# Tiva_Control.net
KiCad netlist of a schematic drawn in Altium Designer
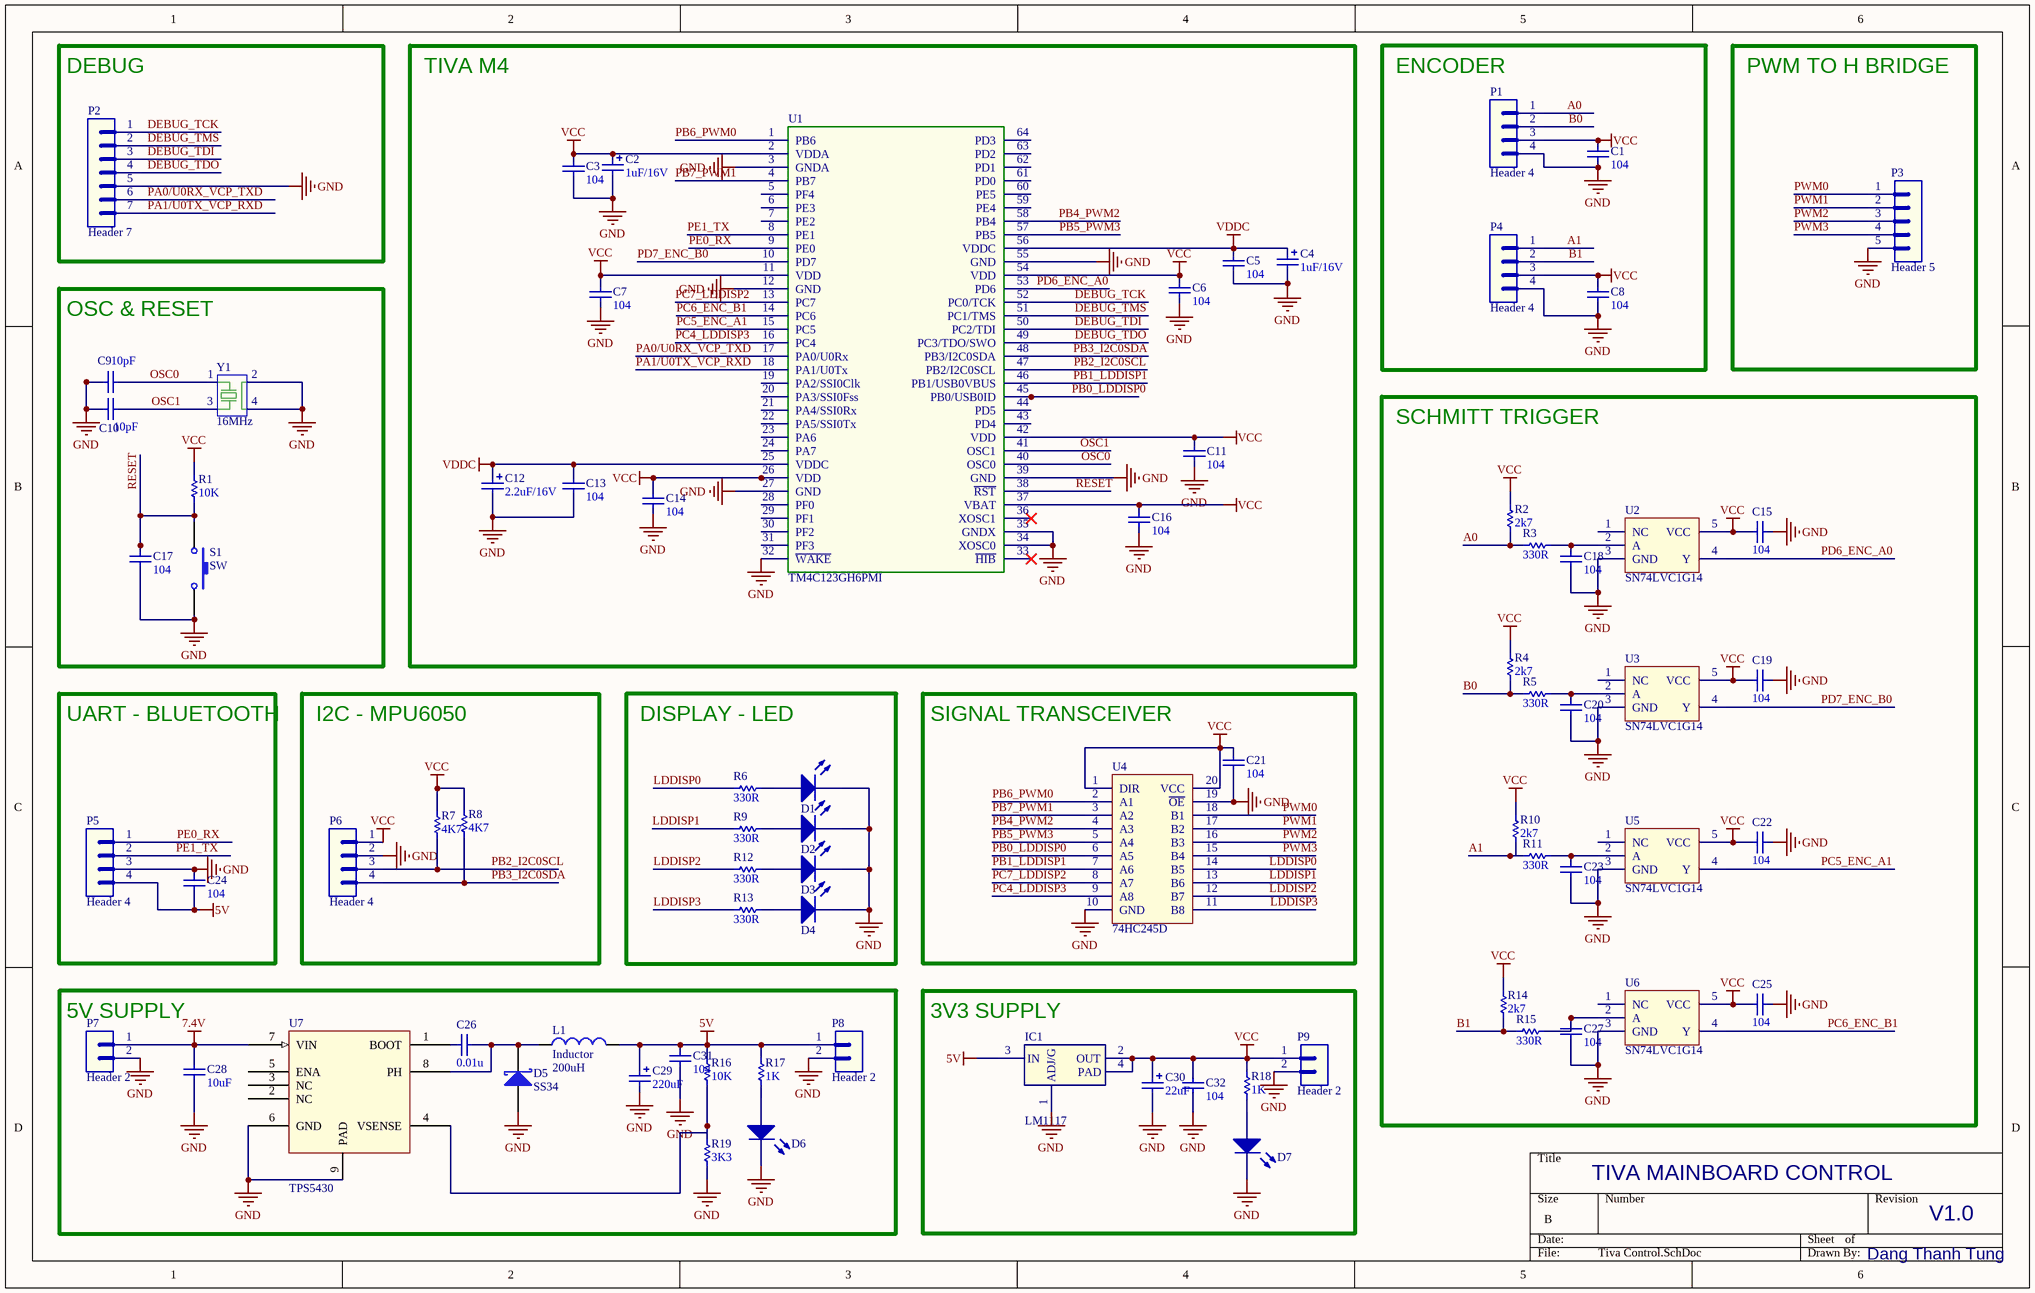
[diagram p0: Tiva Control.SchDoc]

(export (version "E")
  (design (tool "Eeschema 10.0.6"))
  (components
    (comp (ref "C1")
      (value "104")
      (footprint "CAP-SM-0805")
      (description "Capacitor")
      (fields (field (name "Comment") "Cap Non-Pol SMD"))
      (libsource (lib "minht57_lib") (part "Cap Non-Pol SMD"))
    )
    (comp (ref "C2")
      (value "Capacitors")
      (footprint "CAP TANTALUM SMD-1206")
      (description "Capacitors Tantalum")
      (fields
        (field (name "MANUFACTURER") "Kemet")
        (field (name "MANUFACTURER PART NUMBER") "T491A106K010AT")
        (field (name "CAPACITANCE") "1uF/16V")
      )
      (libsource (lib "minht57_lib") (part "Cap Pol Tantalum"))
    )
    (comp (ref "C3")
      (value "104")
      (footprint "CAP-SM-0805")
      (description "Capacitor")
      (fields (field (name "Comment") "Cap Non-Pol SMD"))
      (libsource (lib "minht57_lib") (part "Cap Non-Pol SMD"))
    )
    (comp (ref "C4")
      (value "Capacitors")
      (footprint "CAP TANTALUM SMD-1206")
      (description "Capacitors Tantalum")
      (fields
        (field (name "MANUFACTURER") "Kemet")
        (field (name "MANUFACTURER PART NUMBER") "T491A106K010AT")
        (field (name "CAPACITANCE") "1uF/16V")
      )
      (libsource (lib "minht57_lib") (part "Cap Pol Tantalum"))
    )
    (comp (ref "C5")
      (value "104")
      (footprint "CAP-SM-0805")
      (description "Capacitor")
      (fields (field (name "Comment") "Cap Non-Pol SMD"))
      (libsource (lib "minht57_lib") (part "Cap Non-Pol SMD"))
    )
    (comp (ref "C6")
      (value "104")
      (footprint "CAP-SM-0805")
      (description "Capacitor")
      (fields (field (name "Comment") "Cap Non-Pol SMD"))
      (libsource (lib "minht57_lib") (part "Cap Non-Pol SMD"))
    )
    (comp (ref "C7")
      (value "104")
      (footprint "CAP-SM-0805")
      (description "Capacitor")
      (fields (field (name "Comment") "Cap Non-Pol SMD"))
      (libsource (lib "minht57_lib") (part "Cap Non-Pol SMD"))
    )
    (comp (ref "C8")
      (value "104")
      (footprint "CAP-SM-0805")
      (description "Capacitor")
      (fields (field (name "Comment") "Cap Non-Pol SMD"))
      (libsource (lib "minht57_lib") (part "Cap Non-Pol SMD"))
    )
    (comp (ref "C9")
      (value "10pF")
      (footprint "CAP-SM-0805")
      (description "Capacitor")
      (fields (field (name "Comment") "Cap Non-Pol SMD"))
      (libsource (lib "minht57_lib") (part "Cap Non-Pol SMD"))
    )
    (comp (ref "C10")
      (value "10pF")
      (footprint "CAP-SM-0805")
      (description "Capacitor")
      (fields (field (name "Comment") "Cap Non-Pol SMD"))
      (libsource (lib "minht57_lib") (part "Cap Non-Pol SMD"))
    )
    (comp (ref "C11")
      (value "104")
      (footprint "CAP-SM-0805")
      (description "Capacitor")
      (fields (field (name "Comment") "Cap Non-Pol SMD"))
      (libsource (lib "minht57_lib") (part "Cap Non-Pol SMD"))
    )
    (comp (ref "C12")
      (value "Capacitors")
      (footprint "CAP TANTALUM SMD-1206")
      (description "Capacitors Tantalum")
      (fields
        (field (name "MANUFACTURER") "Kemet")
        (field (name "MANUFACTURER PART NUMBER") "T491A106K010AT")
        (field (name "CAPACITANCE") "2.2uF/16V")
      )
      (libsource (lib "minht57_lib") (part "Cap Pol Tantalum"))
    )
    (comp (ref "C13")
      (value "104")
      (footprint "CAP-SM-0805")
      (description "Capacitor")
      (fields (field (name "Comment") "Cap Non-Pol SMD"))
      (libsource (lib "minht57_lib") (part "Cap Non-Pol SMD"))
    )
    (comp (ref "C14")
      (value "104")
      (footprint "CAP-SM-0805")
      (description "Capacitor")
      (fields (field (name "Comment") "Cap Non-Pol SMD"))
      (libsource (lib "minht57_lib") (part "Cap Non-Pol SMD"))
    )
    (comp (ref "C15")
      (value "104")
      (footprint "CAP-SM-0805")
      (description "Capacitor")
      (fields (field (name "Comment") "Cap Non-Pol SMD"))
      (libsource (lib "minht57_lib") (part "Cap Non-Pol SMD"))
    )
    (comp (ref "C16")
      (value "104")
      (footprint "CAP-SM-0805")
      (description "Capacitor")
      (fields (field (name "Comment") "Cap Non-Pol SMD"))
      (libsource (lib "minht57_lib") (part "Cap Non-Pol SMD"))
    )
    (comp (ref "C17")
      (value "104")
      (footprint "CAP-SM-0805")
      (description "Capacitor")
      (fields (field (name "Comment") "Cap Non-Pol SMD"))
      (libsource (lib "minht57_lib") (part "Cap Non-Pol SMD"))
    )
    (comp (ref "C18")
      (value "104")
      (footprint "CAP-SM-0805")
      (description "Capacitor")
      (fields (field (name "Comment") "Cap Non-Pol SMD"))
      (libsource (lib "minht57_lib") (part "Cap Non-Pol SMD"))
    )
    (comp (ref "C19")
      (value "104")
      (footprint "CAP-SM-0805")
      (description "Capacitor")
      (fields (field (name "Comment") "Cap Non-Pol SMD"))
      (libsource (lib "minht57_lib") (part "Cap Non-Pol SMD"))
    )
    (comp (ref "C20")
      (value "104")
      (footprint "CAP-SM-0805")
      (description "Capacitor")
      (fields (field (name "Comment") "Cap Non-Pol SMD"))
      (libsource (lib "minht57_lib") (part "Cap Non-Pol SMD"))
    )
    (comp (ref "C21")
      (value "104")
      (footprint "CAP-SM-0805")
      (description "Capacitor")
      (fields (field (name "Comment") "Cap Non-Pol SMD"))
      (libsource (lib "minht57_lib") (part "Cap Non-Pol SMD"))
    )
    (comp (ref "C22")
      (value "104")
      (footprint "CAP-SM-0805")
      (description "Capacitor")
      (fields (field (name "Comment") "Cap Non-Pol SMD"))
      (libsource (lib "minht57_lib") (part "Cap Non-Pol SMD"))
    )
    (comp (ref "C23")
      (value "104")
      (footprint "CAP-SM-0805")
      (description "Capacitor")
      (fields (field (name "Comment") "Cap Non-Pol SMD"))
      (libsource (lib "minht57_lib") (part "Cap Non-Pol SMD"))
    )
    (comp (ref "C24")
      (value "104")
      (footprint "CAP-SM-0805")
      (description "Capacitor")
      (fields (field (name "Comment") "Cap Non-Pol SMD"))
      (libsource (lib "minht57_lib") (part "Cap Non-Pol SMD"))
    )
    (comp (ref "C25")
      (value "104")
      (footprint "CAP-SM-0805")
      (description "Capacitor")
      (fields (field (name "Comment") "Cap Non-Pol SMD"))
      (libsource (lib "minht57_lib") (part "Cap Non-Pol SMD"))
    )
    (comp (ref "C26")
      (value "0.01u")
      (footprint "CAP-SM-0805")
      (description "Capacitor")
      (fields (field (name "Comment") "Cap Non-Pol SMD"))
      (libsource (lib "minht57_lib") (part "Cap Non-Pol SMD"))
    )
    (comp (ref "C27")
      (value "104")
      (footprint "CAP-SM-0805")
      (description "Capacitor")
      (fields (field (name "Comment") "Cap Non-Pol SMD"))
      (libsource (lib "minht57_lib") (part "Cap Non-Pol SMD"))
    )
    (comp (ref "C28")
      (value "10uF")
      (footprint "CAP-SM-0805")
      (description "Capacitor")
      (fields (field (name "Comment") "Cap Non-Pol SMD"))
      (libsource (lib "minht57_lib") (part "Cap Non-Pol SMD"))
    )
    (comp (ref "C29")
      (value "220uF")
      (footprint "CAP ALU SIZE D")
      (description "Polarized Capacitor (Radial)")
      (fields (field (name "Comment") "Cap Pol SMD"))
      (libsource (lib "minht57_lib") (part "Cap Pol SMD"))
    )
    (comp (ref "C30")
      (value "22uF")
      (footprint "CAP ALU SIZE B")
      (description "Polarized Capacitor (Radial)")
      (fields (field (name "Comment") "Cap Pol SMD"))
      (libsource (lib "minht57_lib") (part "Cap Pol SMD"))
    )
    (comp (ref "C31")
      (value "104")
      (footprint "CAP-SM-0805")
      (description "Capacitor")
      (fields (field (name "Comment") "Cap Non-Pol SMD"))
      (libsource (lib "minht57_lib") (part "Cap Non-Pol SMD"))
    )
    (comp (ref "C32")
      (value "104")
      (footprint "CAP-SM-0805")
      (description "Capacitor")
      (fields (field (name "Comment") "Cap Non-Pol SMD"))
      (libsource (lib "minht57_lib") (part "Cap Non-Pol SMD"))
    )
    (comp (ref "D1")
      (value "LED SMD")
      (footprint "LED_0805_Blue")
      (description "LED")
      (libsource (lib "minht57_lib") (part "LED SMD"))
    )
    (comp (ref "D2")
      (value "LED SMD")
      (footprint "LED_0805_Blue")
      (description "LED")
      (libsource (lib "minht57_lib") (part "LED SMD"))
    )
    (comp (ref "D3")
      (value "LED SMD")
      (footprint "LED_0805_Blue")
      (description "LED")
      (libsource (lib "minht57_lib") (part "LED SMD"))
    )
    (comp (ref "D4")
      (value "LED SMD")
      (footprint "LED_0805_Blue")
      (description "LED")
      (libsource (lib "minht57_lib") (part "LED SMD"))
    )
    (comp (ref "D5")
      (value "SS34")
      (footprint "SS34")
      (description "Schottky Diode")
      (fields (field (name "PUBLISHER") "Altium Limited"))
      (libsource (lib "minht57_lib") (part "D Schottky"))
    )
    (comp (ref "D6")
      (value "LED SMD")
      (footprint "LED_0805_Blue")
      (description "LED")
      (libsource (lib "minht57_lib") (part "LED SMD"))
    )
    (comp (ref "D7")
      (value "LED SMD")
      (footprint "LED_0805_Blue")
      (description "LED")
      (libsource (lib "minht57_lib") (part "LED SMD"))
    )
    (comp (ref "IC1")
      (value "LM1117")
      (footprint "SOT223-4N")
      (description "Available in 1.8V, 2.5V, 2.85V, 3.3V, 5V, and  Adjustable Versions")
      (libsource (lib "minht57_lib") (part "LM1117"))
    )
    (comp (ref "L1")
      (value "Inductor")
      (footprint "INDUCTOR 12.5x12.5")
      (fields (field (name "ALTIUM_VALUE") "200uH"))
      (libsource (lib "minht57_lib") (part "Inductor"))
    )
    (comp (ref "P1")
      (value "Header 4")
      (footprint "JP4")
      (description "Header, 4-Pin")
      (fields (field (name "PUBLISHER") "Altium Limited"))
      (libsource (lib "minht57_lib") (part "Header 4"))
    )
    (comp (ref "P2")
      (value "Header 7")
      (footprint "JP7")
      (description "Header, 7-Pin")
      (fields (field (name "PUBLISHER") "Altium Limited"))
      (libsource (lib "minht57_lib") (part "Header 7"))
    )
    (comp (ref "P3")
      (value "Header 5")
      (footprint "JP5")
      (description "Header, 5-Pin")
      (fields (field (name "PUBLISHER") "Altium Limited"))
      (libsource (lib "minht57_lib") (part "Header 5"))
    )
    (comp (ref "P4")
      (value "Header 4")
      (footprint "JP4")
      (description "Header, 4-Pin")
      (fields (field (name "PUBLISHER") "Altium Limited"))
      (libsource (lib "minht57_lib") (part "Header 4"))
    )
    (comp (ref "P5")
      (value "Header 4")
      (footprint "JP4")
      (description "Header, 4-Pin")
      (fields (field (name "PUBLISHER") "Altium Limited"))
      (libsource (lib "minht57_lib") (part "Header 4"))
    )
    (comp (ref "P6")
      (value "Header 4")
      (footprint "JP4")
      (description "Header, 4-Pin")
      (fields (field (name "PUBLISHER") "Altium Limited"))
      (libsource (lib "minht57_lib") (part "Header 4"))
    )
    (comp (ref "P7")
      (value "Header 2")
      (footprint "JP2")
      (description "Header, 2-Pin")
      (fields (field (name "PUBLISHER") "Altium Limited"))
      (libsource (lib "") (part "Header 2_1"))
    )
    (comp (ref "P8")
      (value "Header 2")
      (footprint "JP2")
      (description "Header, 2-Pin")
      (fields (field (name "PUBLISHER") "Altium Limited"))
      (libsource (lib "minht57_lib") (part "Header 2"))
    )
    (comp (ref "P9")
      (value "Header 2")
      (footprint "JP2")
      (description "Header, 2-Pin")
      (fields (field (name "PUBLISHER") "Altium Limited"))
      (libsource (lib "minht57_lib") (part "Header 2"))
    )
    (comp (ref "R1")
      (value "10K")
      (footprint "RES-SM-0805")
      (description "Resistor")
      (fields (field (name "Comment") "Res SMD"))
      (libsource (lib "minht57_lib") (part "Res SMD"))
    )
    (comp (ref "R2")
      (value "2k7")
      (footprint "RES-SM-0805")
      (description "Resistor")
      (fields (field (name "Comment") "Res SMD"))
      (libsource (lib "minht57_lib") (part "Res SMD"))
    )
    (comp (ref "R3")
      (value "330R")
      (footprint "RES-SM-0805")
      (description "Resistor")
      (fields (field (name "Comment") "Res SMD"))
      (libsource (lib "minht57_lib") (part "Res SMD"))
    )
    (comp (ref "R4")
      (value "2k7")
      (footprint "RES-SM-0805")
      (description "Resistor")
      (fields (field (name "Comment") "Res SMD"))
      (libsource (lib "minht57_lib") (part "Res SMD"))
    )
    (comp (ref "R5")
      (value "330R")
      (footprint "RES-SM-0805")
      (description "Resistor")
      (fields (field (name "Comment") "Res SMD"))
      (libsource (lib "minht57_lib") (part "Res SMD"))
    )
    (comp (ref "R6")
      (value "330R")
      (footprint "RES-SM-0805")
      (description "Resistor")
      (fields (field (name "Comment") "Res SMD"))
      (libsource (lib "minht57_lib") (part "Res SMD"))
    )
    (comp (ref "R7")
      (value "4K7")
      (footprint "RES-SM-0805")
      (description "Resistor")
      (fields (field (name "Comment") "Res SMD"))
      (libsource (lib "minht57_lib") (part "Res SMD"))
    )
    (comp (ref "R8")
      (value "4K7")
      (footprint "RES-SM-0805")
      (description "Resistor")
      (fields (field (name "Comment") "Res SMD"))
      (libsource (lib "minht57_lib") (part "Res SMD"))
    )
    (comp (ref "R9")
      (value "330R")
      (footprint "RES-SM-0805")
      (description "Resistor")
      (fields (field (name "Comment") "Res SMD"))
      (libsource (lib "minht57_lib") (part "Res SMD"))
    )
    (comp (ref "R10")
      (value "2k7")
      (footprint "RES-SM-0805")
      (description "Resistor")
      (fields (field (name "Comment") "Res SMD"))
      (libsource (lib "minht57_lib") (part "Res SMD"))
    )
    (comp (ref "R11")
      (value "330R")
      (footprint "RES-SM-0805")
      (description "Resistor")
      (fields (field (name "Comment") "Res SMD"))
      (libsource (lib "minht57_lib") (part "Res SMD"))
    )
    (comp (ref "R12")
      (value "330R")
      (footprint "RES-SM-0805")
      (description "Resistor")
      (fields (field (name "Comment") "Res SMD"))
      (libsource (lib "minht57_lib") (part "Res SMD"))
    )
    (comp (ref "R13")
      (value "330R")
      (footprint "RES-SM-0805")
      (description "Resistor")
      (fields (field (name "Comment") "Res SMD"))
      (libsource (lib "minht57_lib") (part "Res SMD"))
    )
    (comp (ref "R14")
      (value "2k7")
      (footprint "RES-SM-0805")
      (description "Resistor")
      (fields (field (name "Comment") "Res SMD"))
      (libsource (lib "minht57_lib") (part "Res SMD"))
    )
    (comp (ref "R15")
      (value "330R")
      (footprint "RES-SM-0805")
      (description "Resistor")
      (fields (field (name "Comment") "Res SMD"))
      (libsource (lib "minht57_lib") (part "Res SMD"))
    )
    (comp (ref "R16")
      (value "10K")
      (footprint "RES-SM-0805")
      (description "Resistor")
      (fields (field (name "Comment") "Res SMD"))
      (libsource (lib "minht57_lib") (part "Res SMD"))
    )
    (comp (ref "R17")
      (value "1K")
      (footprint "RES-SM-0805")
      (description "Resistor")
      (fields (field (name "Comment") "Res SMD"))
      (libsource (lib "minht57_lib") (part "Res SMD"))
    )
    (comp (ref "R18")
      (value "1K")
      (footprint "RES-SM-0805")
      (description "Resistor")
      (fields (field (name "Comment") "Res SMD"))
      (libsource (lib "minht57_lib") (part "Res SMD"))
    )
    (comp (ref "R19")
      (value "3K3")
      (footprint "RES-SM-0805")
      (description "Resistor")
      (fields (field (name "Comment") "Res SMD"))
      (libsource (lib "minht57_lib") (part "Res SMD"))
    )
    (comp (ref "S1")
      (value "SW")
      (footprint "SW-SMD")
      (description "Switch button 2 pin")
      (libsource (lib "minht57_lib") (part "Tact SW - 2Pin"))
    )
    (comp (ref "U1")
      (value "TM4C123GH6PMI")
      (footprint "S-PQFP-G64")
      (fields (field (name "MANUFACTURER") "TEXAS INSTRUMENTS"))
      (libsource (lib "minht57_lib") (part "TM4C123GH6PMI"))
    )
    (comp (ref "U2")
      (value "SN74LVC1G14")
      (footprint "SOT23-5N")
      (libsource (lib "minht57_lib") (part "SN74LVC1G14"))
    )
    (comp (ref "U3")
      (value "SN74LVC1G14")
      (footprint "SOT23-5N")
      (libsource (lib "minht57_lib") (part "SN74LVC1G14"))
    )
    (comp (ref "U4")
      (value "74HC245D")
      (footprint "SOIC127P1030X265-20M")
      (libsource (lib "minht57_lib") (part "74HC245D"))
    )
    (comp (ref "U5")
      (value "SN74LVC1G14")
      (footprint "SOT23-5N")
      (libsource (lib "minht57_lib") (part "SN74LVC1G14"))
    )
    (comp (ref "U6")
      (value "SN74LVC1G14")
      (footprint "SOT23-5N")
      (libsource (lib "minht57_lib") (part "SN74LVC1G14"))
    )
    (comp (ref "U7")
      (value "TPS5430")
      (footprint "DDA8")
      (description "PMIC - Voltage Regulators - DC DC Switching Regulators")
      (fields
        (field (name "MANUFACTURER_PART_NUMBER") "tps5430-ep_dda_8")
        (field (name "GENERIC_PART_NUMBER") "TPS5430-EP")
      )
      (libsource (lib "minht57_lib") (part "TPS5430"))
    )
    (comp (ref "Y1")
      (value "16MHz")
      (footprint "Crystal SMD 2.5X2.0")
      (description "Crystal For all Crystal 2pin")
      (libsource (lib "minht57_lib") (part "XTAL 4Pin SMD"))
    )
  )
  (nets
    (net (code "1") (name "/A0") (class "Default")
      (node (ref "P1") (pin "1") (pinfunction "1_1") (pintype "passive"))
      (node (ref "R2") (pin "1") (pinfunction "1_1") (pintype "passive"))
      (node (ref "R3") (pin "1") (pinfunction "1_1") (pintype "passive"))
    )
    (net (code "2") (name "/A1") (class "Default")
      (node (ref "P4") (pin "1") (pinfunction "1_1") (pintype "passive"))
      (node (ref "R10") (pin "1") (pinfunction "1_1") (pintype "passive"))
      (node (ref "R11") (pin "1") (pinfunction "1_1") (pintype "passive"))
    )
    (net (code "3") (name "/B0") (class "Default")
      (node (ref "P1") (pin "2") (pinfunction "2_2") (pintype "passive"))
      (node (ref "R4") (pin "1") (pinfunction "1_1") (pintype "passive"))
      (node (ref "R5") (pin "1") (pinfunction "1_1") (pintype "passive"))
    )
    (net (code "4") (name "/B1") (class "Default")
      (node (ref "P4") (pin "2") (pinfunction "2_2") (pintype "passive"))
      (node (ref "R14") (pin "1") (pinfunction "1_1") (pintype "passive"))
      (node (ref "R15") (pin "1") (pinfunction "1_1") (pintype "passive"))
    )
    (net (code "5") (name "/DEBUG_TCK") (class "Default")
      (node (ref "P2") (pin "1") (pinfunction "1_1") (pintype "passive"))
      (node (ref "U1") (pin "52") (pinfunction "PC0/TCK_52") (pintype "passive"))
    )
    (net (code "6") (name "/DEBUG_TDI") (class "Default")
      (node (ref "P2") (pin "3") (pinfunction "3_3") (pintype "passive"))
      (node (ref "U1") (pin "50") (pinfunction "PC2/TDI_50") (pintype "passive"))
    )
    (net (code "7") (name "/DEBUG_TDO") (class "Default")
      (node (ref "P2") (pin "4") (pinfunction "4_4") (pintype "passive"))
      (node (ref "U1") (pin "49") (pinfunction "PC3/TDO/SWO_49") (pintype "passive"))
    )
    (net (code "8") (name "/DEBUG_TMS") (class "Default")
      (node (ref "P2") (pin "2") (pinfunction "2_2") (pintype "passive"))
      (node (ref "U1") (pin "51") (pinfunction "PC1/TMS_51") (pintype "passive"))
    )
    (net (code "9") (name "/LDDISP0") (class "Default")
      (node (ref "R6") (pin "1") (pinfunction "1_1") (pintype "passive"))
      (node (ref "U4") (pin "14") (pinfunction "B5_14") (pintype "passive"))
    )
    (net (code "10") (name "/LDDISP1") (class "Default")
      (node (ref "R9") (pin "1") (pinfunction "1_1") (pintype "passive"))
      (node (ref "U4") (pin "13") (pinfunction "B6_13") (pintype "passive"))
    )
    (net (code "11") (name "/LDDISP2") (class "Default")
      (node (ref "R12") (pin "1") (pinfunction "1_1") (pintype "passive"))
      (node (ref "U4") (pin "12") (pinfunction "B7_12") (pintype "passive"))
    )
    (net (code "12") (name "/LDDISP3") (class "Default")
      (node (ref "R13") (pin "1") (pinfunction "1_1") (pintype "passive"))
      (node (ref "U4") (pin "11") (pinfunction "B8_11") (pintype "passive"))
    )
    (net (code "13") (name "/OSC0") (class "Default")
      (node (ref "C9") (pin "2") (pinfunction "2_2") (pintype "passive"))
      (node (ref "U1") (pin "40") (pinfunction "OSC0_40") (pintype "passive"))
      (node (ref "Y1") (pin "1") (pinfunction "1_1") (pintype "passive"))
    )
    (net (code "14") (name "/OSC1") (class "Default")
      (node (ref "C10") (pin "2") (pinfunction "2_2") (pintype "passive"))
      (node (ref "U1") (pin "41") (pinfunction "OSC1_41") (pintype "passive"))
      (node (ref "Y1") (pin "3") (pinfunction "3_3") (pintype "passive"))
    )
    (net (code "15") (name "/PA0{slash}U0RX_VCP_TXD") (class "Default")
      (node (ref "P2") (pin "6") (pinfunction "6_6") (pintype "passive"))
      (node (ref "U1") (pin "17") (pinfunction "PA0/U0Rx_17") (pintype "passive"))
    )
    (net (code "16") (name "/PA1{slash}U0TX_VCP_RXD") (class "Default")
      (node (ref "P2") (pin "7") (pinfunction "7_7") (pintype "passive"))
      (node (ref "U1") (pin "18") (pinfunction "PA1/U0Tx_18") (pintype "passive"))
    )
    (net (code "17") (name "/PB0_LDDISP0") (class "Default")
      (node (ref "U1") (pin "45") (pinfunction "PB0/USB0ID_45") (pintype "passive"))
      (node (ref "U4") (pin "6") (pinfunction "A5_6") (pintype "passive"))
    )
    (net (code "18") (name "/PB1_LDDISP1") (class "Default")
      (node (ref "U1") (pin "46") (pinfunction "PB1/USB0VBUS_46") (pintype "passive"))
      (node (ref "U4") (pin "7") (pinfunction "A6_7") (pintype "passive"))
    )
    (net (code "19") (name "/PB2_I2C0SCL") (class "Default")
      (node (ref "P6") (pin "3") (pinfunction "3_3") (pintype "passive"))
      (node (ref "R7") (pin "1") (pinfunction "1_1") (pintype "passive"))
      (node (ref "U1") (pin "47") (pinfunction "PB2/I2C0SCL_47") (pintype "passive"))
    )
    (net (code "20") (name "/PB3_I2C0SDA") (class "Default")
      (node (ref "P6") (pin "4") (pinfunction "4_4") (pintype "passive"))
      (node (ref "R8") (pin "1") (pinfunction "1_1") (pintype "passive"))
      (node (ref "U1") (pin "48") (pinfunction "PB3/I2C0SDA_48") (pintype "passive"))
    )
    (net (code "21") (name "/PB4_PWM2") (class "Default")
      (node (ref "U1") (pin "58") (pinfunction "PB4_58") (pintype "passive"))
      (node (ref "U4") (pin "4") (pinfunction "A3_4") (pintype "passive"))
    )
    (net (code "22") (name "/PB5_PWM3") (class "Default")
      (node (ref "U1") (pin "57") (pinfunction "PB5_57") (pintype "passive"))
      (node (ref "U4") (pin "5") (pinfunction "A4_5") (pintype "passive"))
    )
    (net (code "23") (name "/PB6_PWM0") (class "Default")
      (node (ref "U1") (pin "1") (pinfunction "PB6_1") (pintype "passive"))
      (node (ref "U4") (pin "2") (pinfunction "A1_2") (pintype "passive"))
    )
    (net (code "24") (name "/PB7_PWM1") (class "Default")
      (node (ref "U1") (pin "4") (pinfunction "PB7_4") (pintype "passive"))
      (node (ref "U4") (pin "3") (pinfunction "A2_3") (pintype "passive"))
    )
    (net (code "25") (name "/PC4_LDDISP3") (class "Default")
      (node (ref "U1") (pin "16") (pinfunction "PC4_16") (pintype "passive"))
      (node (ref "U4") (pin "9") (pinfunction "A8_9") (pintype "passive"))
    )
    (net (code "26") (name "/PC5_ENC_A1") (class "Default")
      (node (ref "U1") (pin "15") (pinfunction "PC5_15") (pintype "passive"))
      (node (ref "U5") (pin "4") (pinfunction "Y_4") (pintype "passive"))
    )
    (net (code "27") (name "/PC6_ENC_B1") (class "Default")
      (node (ref "U1") (pin "14") (pinfunction "PC6_14") (pintype "passive"))
      (node (ref "U6") (pin "4") (pinfunction "Y_4") (pintype "passive"))
    )
    (net (code "28") (name "/PC7_LDDISP2") (class "Default")
      (node (ref "U1") (pin "13") (pinfunction "PC7_13") (pintype "passive"))
      (node (ref "U4") (pin "8") (pinfunction "A7_8") (pintype "passive"))
    )
    (net (code "29") (name "/PD6_ENC_A0") (class "Default")
      (node (ref "U1") (pin "53") (pinfunction "PD6_53") (pintype "passive"))
      (node (ref "U2") (pin "4") (pinfunction "Y_4") (pintype "passive"))
    )
    (net (code "30") (name "/PD7_ENC_B0") (class "Default")
      (node (ref "U1") (pin "10") (pinfunction "PD7_10") (pintype "passive"))
      (node (ref "U3") (pin "4") (pinfunction "Y_4") (pintype "passive"))
    )
    (net (code "31") (name "/PE0_RX") (class "Default")
      (node (ref "P5") (pin "1") (pinfunction "1_1") (pintype "passive"))
      (node (ref "U1") (pin "9") (pinfunction "PE0_9") (pintype "passive"))
    )
    (net (code "32") (name "/PE1_TX") (class "Default")
      (node (ref "P5") (pin "2") (pinfunction "2_2") (pintype "passive"))
      (node (ref "U1") (pin "8") (pinfunction "PE1_8") (pintype "passive"))
    )
    (net (code "33") (name "/PWM0") (class "Default")
      (node (ref "P3") (pin "1") (pinfunction "1_1") (pintype "passive"))
      (node (ref "U4") (pin "18") (pinfunction "B1_18") (pintype "passive"))
    )
    (net (code "34") (name "/PWM1") (class "Default")
      (node (ref "P3") (pin "2") (pinfunction "2_2") (pintype "passive"))
      (node (ref "U4") (pin "17") (pinfunction "B2_17") (pintype "passive"))
    )
    (net (code "35") (name "/PWM2") (class "Default")
      (node (ref "P3") (pin "3") (pinfunction "3_3") (pintype "passive"))
      (node (ref "U4") (pin "16") (pinfunction "B3_16") (pintype "passive"))
    )
    (net (code "36") (name "/PWM3") (class "Default")
      (node (ref "P3") (pin "4") (pinfunction "4_4") (pintype "passive"))
      (node (ref "U4") (pin "15") (pinfunction "B4_15") (pintype "passive"))
    )
    (net (code "37") (name "/RESET") (class "Default")
      (node (ref "C17") (pin "1") (pinfunction "1_1") (pintype "passive"))
      (node (ref "R1") (pin "1") (pinfunction "1_1") (pintype "passive"))
      (node (ref "S1") (pin "1") (pinfunction "1_1") (pintype "passive"))
      (node (ref "U1") (pin "38") (pinfunction "~{RST}_38") (pintype "passive"))
    )
    (net (code "38") (name "5V") (class "Default")
      (node (ref "C24") (pin "2") (pinfunction "2_2") (pintype "passive"))
      (node (ref "C29") (pin "1") (pinfunction "1_1") (pintype "passive"))
      (node (ref "C31") (pin "1") (pinfunction "1_1") (pintype "passive"))
      (node (ref "IC1") (pin "3") (pinfunction "IN_3") (pintype "passive"))
      (node (ref "L1") (pin "2") (pinfunction "2_2") (pintype "passive"))
      (node (ref "P5") (pin "4") (pinfunction "4_4") (pintype "passive"))
      (node (ref "P8") (pin "1") (pinfunction "1_1") (pintype "passive"))
      (node (ref "R16") (pin "2") (pinfunction "2_2") (pintype "passive"))
      (node (ref "R17") (pin "2") (pinfunction "2_2") (pintype "passive"))
    )
    (net (code "39") (name "7.4V") (class "Default")
      (node (ref "C28") (pin "2") (pinfunction "2_2") (pintype "passive"))
      (node (ref "P7") (pin "1") (pinfunction "1_1") (pintype "passive"))
      (node (ref "U7") (pin "7") (pinfunction "VIN_7") (pintype "input"))
    )
    (net (code "40") (name "GND") (class "Default")
      (node (ref "C1") (pin "2") (pinfunction "2_2") (pintype "passive"))
      (node (ref "C10") (pin "1") (pinfunction "1_1") (pintype "passive"))
      (node (ref "C11") (pin "2") (pinfunction "2_2") (pintype "passive"))
      (node (ref "C12") (pin "2") (pinfunction "2_2") (pintype "passive"))
      (node (ref "C13") (pin "2") (pinfunction "2_2") (pintype "passive"))
      (node (ref "C14") (pin "2") (pinfunction "2_2") (pintype "passive"))
      (node (ref "C15") (pin "2") (pinfunction "2_2") (pintype "passive"))
      (node (ref "C16") (pin "2") (pinfunction "2_2") (pintype "passive"))
      (node (ref "C17") (pin "2") (pinfunction "2_2") (pintype "passive"))
      (node (ref "C18") (pin "1") (pinfunction "1_1") (pintype "passive"))
      (node (ref "C19") (pin "2") (pinfunction "2_2") (pintype "passive"))
      (node (ref "C2") (pin "2") (pinfunction "2_2") (pintype "passive"))
      (node (ref "C20") (pin "1") (pinfunction "1_1") (pintype "passive"))
      (node (ref "C21") (pin "2") (pinfunction "2_2") (pintype "passive"))
      (node (ref "C22") (pin "2") (pinfunction "2_2") (pintype "passive"))
      (node (ref "C23") (pin "1") (pinfunction "1_1") (pintype "passive"))
      (node (ref "C24") (pin "1") (pinfunction "1_1") (pintype "passive"))
      (node (ref "C25") (pin "2") (pinfunction "2_2") (pintype "passive"))
      (node (ref "C27") (pin "1") (pinfunction "1_1") (pintype "passive"))
      (node (ref "C28") (pin "1") (pinfunction "1_1") (pintype "passive"))
      (node (ref "C29") (pin "2") (pinfunction "2_2") (pintype "passive"))
      (node (ref "C3") (pin "2") (pinfunction "2_2") (pintype "passive"))
      (node (ref "C30") (pin "2") (pinfunction "2_2") (pintype "passive"))
      (node (ref "C31") (pin "2") (pinfunction "2_2") (pintype "passive"))
      (node (ref "C32") (pin "2") (pinfunction "2_2") (pintype "passive"))
      (node (ref "C4") (pin "2") (pinfunction "2_2") (pintype "passive"))
      (node (ref "C5") (pin "2") (pinfunction "2_2") (pintype "passive"))
      (node (ref "C6") (pin "2") (pinfunction "2_2") (pintype "passive"))
      (node (ref "C7") (pin "2") (pinfunction "2_2") (pintype "passive"))
      (node (ref "C8") (pin "2") (pinfunction "2_2") (pintype "passive"))
      (node (ref "C9") (pin "1") (pinfunction "1_1") (pintype "passive"))
      (node (ref "D1") (pin "2") (pinfunction "K_2") (pintype "passive"))
      (node (ref "D2") (pin "2") (pinfunction "K_2") (pintype "passive"))
      (node (ref "D3") (pin "2") (pinfunction "K_2") (pintype "passive"))
      (node (ref "D4") (pin "2") (pinfunction "K_2") (pintype "passive"))
      (node (ref "D5") (pin "1") (pinfunction "A_1") (pintype "passive"))
      (node (ref "D6") (pin "2") (pinfunction "K_2") (pintype "passive"))
      (node (ref "D7") (pin "2") (pinfunction "K_2") (pintype "passive"))
      (node (ref "IC1") (pin "1") (pinfunction "ADJ/G_1") (pintype "passive"))
      (node (ref "P1") (pin "4") (pinfunction "4_4") (pintype "passive"))
      (node (ref "P2") (pin "5") (pinfunction "5_5") (pintype "passive"))
      (node (ref "P3") (pin "5") (pinfunction "5_5") (pintype "passive"))
      (node (ref "P4") (pin "4") (pinfunction "4_4") (pintype "passive"))
      (node (ref "P5") (pin "3") (pinfunction "3_3") (pintype "passive"))
      (node (ref "P6") (pin "2") (pinfunction "2_2") (pintype "passive"))
      (node (ref "P7") (pin "2") (pinfunction "2_2") (pintype "passive"))
      (node (ref "P8") (pin "2") (pinfunction "2_2") (pintype "passive"))
      (node (ref "P9") (pin "2") (pinfunction "2_2") (pintype "passive"))
      (node (ref "R19") (pin "1") (pinfunction "1_1") (pintype "passive"))
      (node (ref "S1") (pin "2") (pinfunction "2_2") (pintype "passive"))
      (node (ref "U1") (pin "12") (pinfunction "GND_12") (pintype "passive"))
      (node (ref "U1") (pin "27") (pinfunction "GND_27") (pintype "passive"))
      (node (ref "U1") (pin "3") (pinfunction "GNDA_3") (pintype "passive"))
      (node (ref "U1") (pin "32") (pinfunction "~{WAKE}_32") (pintype "passive"))
      (node (ref "U1") (pin "34") (pinfunction "XOSC0_34") (pintype "passive"))
      (node (ref "U1") (pin "35") (pinfunction "GNDX_35") (pintype "passive"))
      (node (ref "U1") (pin "39") (pinfunction "GND_39") (pintype "passive"))
      (node (ref "U1") (pin "55") (pinfunction "GND_55") (pintype "passive"))
      (node (ref "U2") (pin "3") (pinfunction "GND_3") (pintype "passive"))
      (node (ref "U3") (pin "3") (pinfunction "GND_3") (pintype "passive"))
      (node (ref "U4") (pin "10") (pinfunction "GND_10") (pintype "passive"))
      (node (ref "U4") (pin "19") (pinfunction "~{OE}_19") (pintype "passive"))
      (node (ref "U5") (pin "3") (pinfunction "GND_3") (pintype "passive"))
      (node (ref "U6") (pin "3") (pinfunction "GND_3") (pintype "passive"))
      (node (ref "U7") (pin "6") (pinfunction "GND_6") (pintype "power_in"))
      (node (ref "U7") (pin "9") (pinfunction "PAD_9") (pintype "passive"))
      (node (ref "Y1") (pin "2") (pinfunction "2_2") (pintype "passive"))
      (node (ref "Y1") (pin "4") (pinfunction "4_4") (pintype "passive"))
    )
    (net (code "41") (name "Net-(D1-A)") (class "Default")
      (node (ref "D1") (pin "1") (pinfunction "A_1") (pintype "passive"))
      (node (ref "R6") (pin "2") (pinfunction "2_2") (pintype "passive"))
    )
    (net (code "42") (name "Net-(D2-A)") (class "Default")
      (node (ref "D2") (pin "1") (pinfunction "A_1") (pintype "passive"))
      (node (ref "R9") (pin "2") (pinfunction "2_2") (pintype "passive"))
    )
    (net (code "43") (name "Net-(D3-A)") (class "Default")
      (node (ref "D3") (pin "1") (pinfunction "A_1") (pintype "passive"))
      (node (ref "R12") (pin "2") (pinfunction "2_2") (pintype "passive"))
    )
    (net (code "44") (name "Net-(D4-A)") (class "Default")
      (node (ref "D4") (pin "1") (pinfunction "A_1") (pintype "passive"))
      (node (ref "R13") (pin "2") (pinfunction "2_2") (pintype "passive"))
    )
    (net (code "45") (name "Net-(D5-K)") (class "Default")
      (node (ref "C26") (pin "2") (pinfunction "2_2") (pintype "passive"))
      (node (ref "D5") (pin "2") (pinfunction "K_2") (pintype "passive"))
      (node (ref "L1") (pin "1") (pinfunction "1_1") (pintype "passive"))
      (node (ref "U7") (pin "8") (pinfunction "PH_8") (pintype "passive"))
    )
    (net (code "46") (name "Net-(D6-A)") (class "Default")
      (node (ref "D6") (pin "1") (pinfunction "A_1") (pintype "passive"))
      (node (ref "R17") (pin "1") (pinfunction "1_1") (pintype "passive"))
    )
    (net (code "47") (name "Net-(D7-A)") (class "Default")
      (node (ref "D7") (pin "1") (pinfunction "A_1") (pintype "passive"))
      (node (ref "R18") (pin "1") (pinfunction "1_1") (pintype "passive"))
    )
    (net (code "48") (name "Net-(U2-A)") (class "Default")
      (node (ref "C18") (pin "2") (pinfunction "2_2") (pintype "passive"))
      (node (ref "R3") (pin "2") (pinfunction "2_2") (pintype "passive"))
      (node (ref "U2") (pin "2") (pinfunction "A_2") (pintype "passive"))
    )
    (net (code "49") (name "Net-(U3-A)") (class "Default")
      (node (ref "C20") (pin "2") (pinfunction "2_2") (pintype "passive"))
      (node (ref "R5") (pin "2") (pinfunction "2_2") (pintype "passive"))
      (node (ref "U3") (pin "2") (pinfunction "A_2") (pintype "passive"))
    )
    (net (code "50") (name "Net-(U5-A)") (class "Default")
      (node (ref "C23") (pin "2") (pinfunction "2_2") (pintype "passive"))
      (node (ref "R11") (pin "2") (pinfunction "2_2") (pintype "passive"))
      (node (ref "U5") (pin "2") (pinfunction "A_2") (pintype "passive"))
    )
    (net (code "51") (name "Net-(U6-A)") (class "Default")
      (node (ref "C27") (pin "2") (pinfunction "2_2") (pintype "passive"))
      (node (ref "R15") (pin "2") (pinfunction "2_2") (pintype "passive"))
      (node (ref "U6") (pin "2") (pinfunction "A_2") (pintype "passive"))
    )
    (net (code "52") (name "Net-(U7-BOOT)") (class "Default")
      (node (ref "C26") (pin "1") (pinfunction "1_1") (pintype "passive"))
      (node (ref "U7") (pin "1") (pinfunction "BOOT_1") (pintype "passive"))
    )
    (net (code "53") (name "Net-(U7-VSENSE)") (class "Default")
      (node (ref "R16") (pin "1") (pinfunction "1_1") (pintype "passive"))
      (node (ref "R19") (pin "2") (pinfunction "2_2") (pintype "passive"))
      (node (ref "U7") (pin "4") (pinfunction "VSENSE_4") (pintype "passive"))
    )
    (net (code "54") (name "VCC") (class "Default")
      (node (ref "C1") (pin "1") (pinfunction "1_1") (pintype "passive"))
      (node (ref "C11") (pin "1") (pinfunction "1_1") (pintype "passive"))
      (node (ref "C14") (pin "1") (pinfunction "1_1") (pintype "passive"))
      (node (ref "C15") (pin "1") (pinfunction "1_1") (pintype "passive"))
      (node (ref "C16") (pin "1") (pinfunction "1_1") (pintype "passive"))
      (node (ref "C19") (pin "1") (pinfunction "1_1") (pintype "passive"))
      (node (ref "C2") (pin "1") (pinfunction "1_1") (pintype "passive"))
      (node (ref "C21") (pin "1") (pinfunction "1_1") (pintype "passive"))
      (node (ref "C22") (pin "1") (pinfunction "1_1") (pintype "passive"))
      (node (ref "C25") (pin "1") (pinfunction "1_1") (pintype "passive"))
      (node (ref "C3") (pin "1") (pinfunction "1_1") (pintype "passive"))
      (node (ref "C30") (pin "1") (pinfunction "1_1") (pintype "passive"))
      (node (ref "C32") (pin "1") (pinfunction "1_1") (pintype "passive"))
      (node (ref "C6") (pin "1") (pinfunction "1_1") (pintype "passive"))
      (node (ref "C7") (pin "1") (pinfunction "1_1") (pintype "passive"))
      (node (ref "C8") (pin "1") (pinfunction "1_1") (pintype "passive"))
      (node (ref "IC1") (pin "2") (pinfunction "OUT_2") (pintype "passive"))
      (node (ref "IC1") (pin "4") (pinfunction "PAD_4") (pintype "passive"))
      (node (ref "P1") (pin "3") (pinfunction "3_3") (pintype "passive"))
      (node (ref "P4") (pin "3") (pinfunction "3_3") (pintype "passive"))
      (node (ref "P6") (pin "1") (pinfunction "1_1") (pintype "passive"))
      (node (ref "P9") (pin "1") (pinfunction "1_1") (pintype "passive"))
      (node (ref "R1") (pin "2") (pinfunction "2_2") (pintype "passive"))
      (node (ref "R10") (pin "2") (pinfunction "2_2") (pintype "passive"))
      (node (ref "R14") (pin "2") (pinfunction "2_2") (pintype "passive"))
      (node (ref "R18") (pin "2") (pinfunction "2_2") (pintype "passive"))
      (node (ref "R2") (pin "2") (pinfunction "2_2") (pintype "passive"))
      (node (ref "R4") (pin "2") (pinfunction "2_2") (pintype "passive"))
      (node (ref "R7") (pin "2") (pinfunction "2_2") (pintype "passive"))
      (node (ref "R8") (pin "2") (pinfunction "2_2") (pintype "passive"))
      (node (ref "U1") (pin "11") (pinfunction "VDD_11") (pintype "passive"))
      (node (ref "U1") (pin "2") (pinfunction "VDDA_2") (pintype "passive"))
      (node (ref "U1") (pin "26") (pinfunction "VDD_26") (pintype "passive"))
      (node (ref "U1") (pin "37") (pinfunction "VBAT_37") (pintype "passive"))
      (node (ref "U1") (pin "42") (pinfunction "VDD_42") (pintype "passive"))
      (node (ref "U1") (pin "54") (pinfunction "VDD_54") (pintype "passive"))
      (node (ref "U2") (pin "5") (pinfunction "VCC_5") (pintype "passive"))
      (node (ref "U3") (pin "5") (pinfunction "VCC_5") (pintype "passive"))
      (node (ref "U4") (pin "1") (pinfunction "DIR_1") (pintype "passive"))
      (node (ref "U4") (pin "20") (pinfunction "VCC_20") (pintype "passive"))
      (node (ref "U5") (pin "5") (pinfunction "VCC_5") (pintype "passive"))
      (node (ref "U6") (pin "5") (pinfunction "VCC_5") (pintype "passive"))
    )
    (net (code "55") (name "VDDC") (class "Default")
      (node (ref "C12") (pin "1") (pinfunction "1_1") (pintype "passive"))
      (node (ref "C13") (pin "1") (pinfunction "1_1") (pintype "passive"))
      (node (ref "C4") (pin "1") (pinfunction "1_1") (pintype "passive"))
      (node (ref "C5") (pin "1") (pinfunction "1_1") (pintype "passive"))
      (node (ref "U1") (pin "25") (pinfunction "VDDC_25") (pintype "passive"))
      (node (ref "U1") (pin "56") (pinfunction "VDDC_56") (pintype "passive"))
    )
    (net (code "56") (name "unconnected-(U1-PA2{slash}SSI0Clk-Pad19)") (class "Default")
      (node (ref "U1") (pin "19") (pinfunction "PA2/SSI0Clk_19") (pintype "passive"))
    )
    (net (code "57") (name "unconnected-(U1-PA3{slash}SSI0Fss-Pad20)") (class "Default")
      (node (ref "U1") (pin "20") (pinfunction "PA3/SSI0Fss_20") (pintype "passive"))
    )
    (net (code "58") (name "unconnected-(U1-PA4{slash}SSI0Rx-Pad21)") (class "Default")
      (node (ref "U1") (pin "21") (pinfunction "PA4/SSI0Rx_21") (pintype "passive"))
    )
    (net (code "59") (name "unconnected-(U1-PA5{slash}SSI0Tx-Pad22)") (class "Default")
      (node (ref "U1") (pin "22") (pinfunction "PA5/SSI0Tx_22") (pintype "passive"))
    )
    (net (code "60") (name "unconnected-(U1-PA6-Pad23)") (class "Default")
      (node (ref "U1") (pin "23") (pinfunction "PA6_23") (pintype "passive"))
    )
    (net (code "61") (name "unconnected-(U1-PA7-Pad24)") (class "Default")
      (node (ref "U1") (pin "24") (pinfunction "PA7_24") (pintype "passive"))
    )
    (net (code "62") (name "unconnected-(U1-PD0-Pad61)") (class "Default")
      (node (ref "U1") (pin "61") (pinfunction "PD0_61") (pintype "passive"))
    )
    (net (code "63") (name "unconnected-(U1-PD1-Pad62)") (class "Default")
      (node (ref "U1") (pin "62") (pinfunction "PD1_62") (pintype "passive"))
    )
    (net (code "64") (name "unconnected-(U1-PD2-Pad63)") (class "Default")
      (node (ref "U1") (pin "63") (pinfunction "PD2_63") (pintype "passive"))
    )
    (net (code "65") (name "unconnected-(U1-PD3-Pad64)") (class "Default")
      (node (ref "U1") (pin "64") (pinfunction "PD3_64") (pintype "passive"))
    )
    (net (code "66") (name "unconnected-(U1-PD4-Pad43)") (class "Default")
      (node (ref "U1") (pin "43") (pinfunction "PD4_43") (pintype "passive"))
    )
    (net (code "67") (name "unconnected-(U1-PD5-Pad44)") (class "Default")
      (node (ref "U1") (pin "44") (pinfunction "PD5_44") (pintype "passive"))
    )
    (net (code "68") (name "unconnected-(U1-PE2-Pad7)") (class "Default")
      (node (ref "U1") (pin "7") (pinfunction "PE2_7") (pintype "passive"))
    )
    (net (code "69") (name "unconnected-(U1-PE3-Pad6)") (class "Default")
      (node (ref "U1") (pin "6") (pinfunction "PE3_6") (pintype "passive"))
    )
    (net (code "70") (name "unconnected-(U1-PE4-Pad59)") (class "Default")
      (node (ref "U1") (pin "59") (pinfunction "PE4_59") (pintype "passive"))
    )
    (net (code "71") (name "unconnected-(U1-PE5-Pad60)") (class "Default")
      (node (ref "U1") (pin "60") (pinfunction "PE5_60") (pintype "passive"))
    )
    (net (code "72") (name "unconnected-(U1-PF0-Pad28)") (class "Default")
      (node (ref "U1") (pin "28") (pinfunction "PF0_28") (pintype "passive"))
    )
    (net (code "73") (name "unconnected-(U1-PF1-Pad29)") (class "Default")
      (node (ref "U1") (pin "29") (pinfunction "PF1_29") (pintype "passive"))
    )
    (net (code "74") (name "unconnected-(U1-PF2-Pad30)") (class "Default")
      (node (ref "U1") (pin "30") (pinfunction "PF2_30") (pintype "passive"))
    )
    (net (code "75") (name "unconnected-(U1-PF3-Pad31)") (class "Default")
      (node (ref "U1") (pin "31") (pinfunction "PF3_31") (pintype "passive"))
    )
    (net (code "76") (name "unconnected-(U1-PF4-Pad5)") (class "Default")
      (node (ref "U1") (pin "5") (pinfunction "PF4_5") (pintype "passive"))
    )
    (net (code "77") (name "unconnected-(U1-XOSC1-Pad36)") (class "Default")
      (node (ref "U1") (pin "36") (pinfunction "XOSC1_36") (pintype "passive+no_connect"))
    )
    (net (code "78") (name "unconnected-(U1-~{HIB}-Pad33)") (class "Default")
      (node (ref "U1") (pin "33") (pinfunction "~{HIB}_33") (pintype "passive+no_connect"))
    )
    (net (code "79") (name "unconnected-(U2-NC-Pad1)") (class "Default")
      (node (ref "U2") (pin "1") (pinfunction "NC_1") (pintype "passive"))
    )
    (net (code "80") (name "unconnected-(U3-NC-Pad1)") (class "Default")
      (node (ref "U3") (pin "1") (pinfunction "NC_1") (pintype "passive"))
    )
    (net (code "81") (name "unconnected-(U5-NC-Pad1)") (class "Default")
      (node (ref "U5") (pin "1") (pinfunction "NC_1") (pintype "passive"))
    )
    (net (code "82") (name "unconnected-(U6-NC-Pad1)") (class "Default")
      (node (ref "U6") (pin "1") (pinfunction "NC_1") (pintype "passive"))
    )
    (net (code "83") (name "unconnected-(U7-ENA-Pad5)") (class "Default")
      (node (ref "U7") (pin "5") (pinfunction "ENA_5") (pintype "passive"))
    )
    (net (code "84") (name "unconnected-(U7-NC-Pad2)") (class "Default")
      (node (ref "U7") (pin "2") (pinfunction "NC_2") (pintype "passive"))
    )
    (net (code "85") (name "unconnected-(U7-NC-Pad3)") (class "Default")
      (node (ref "U7") (pin "3") (pinfunction "NC_3") (pintype "passive"))
    )
  )
)
